# rc360detector_102815.net
KiCad netlist of a schematic drawn in EAGLE
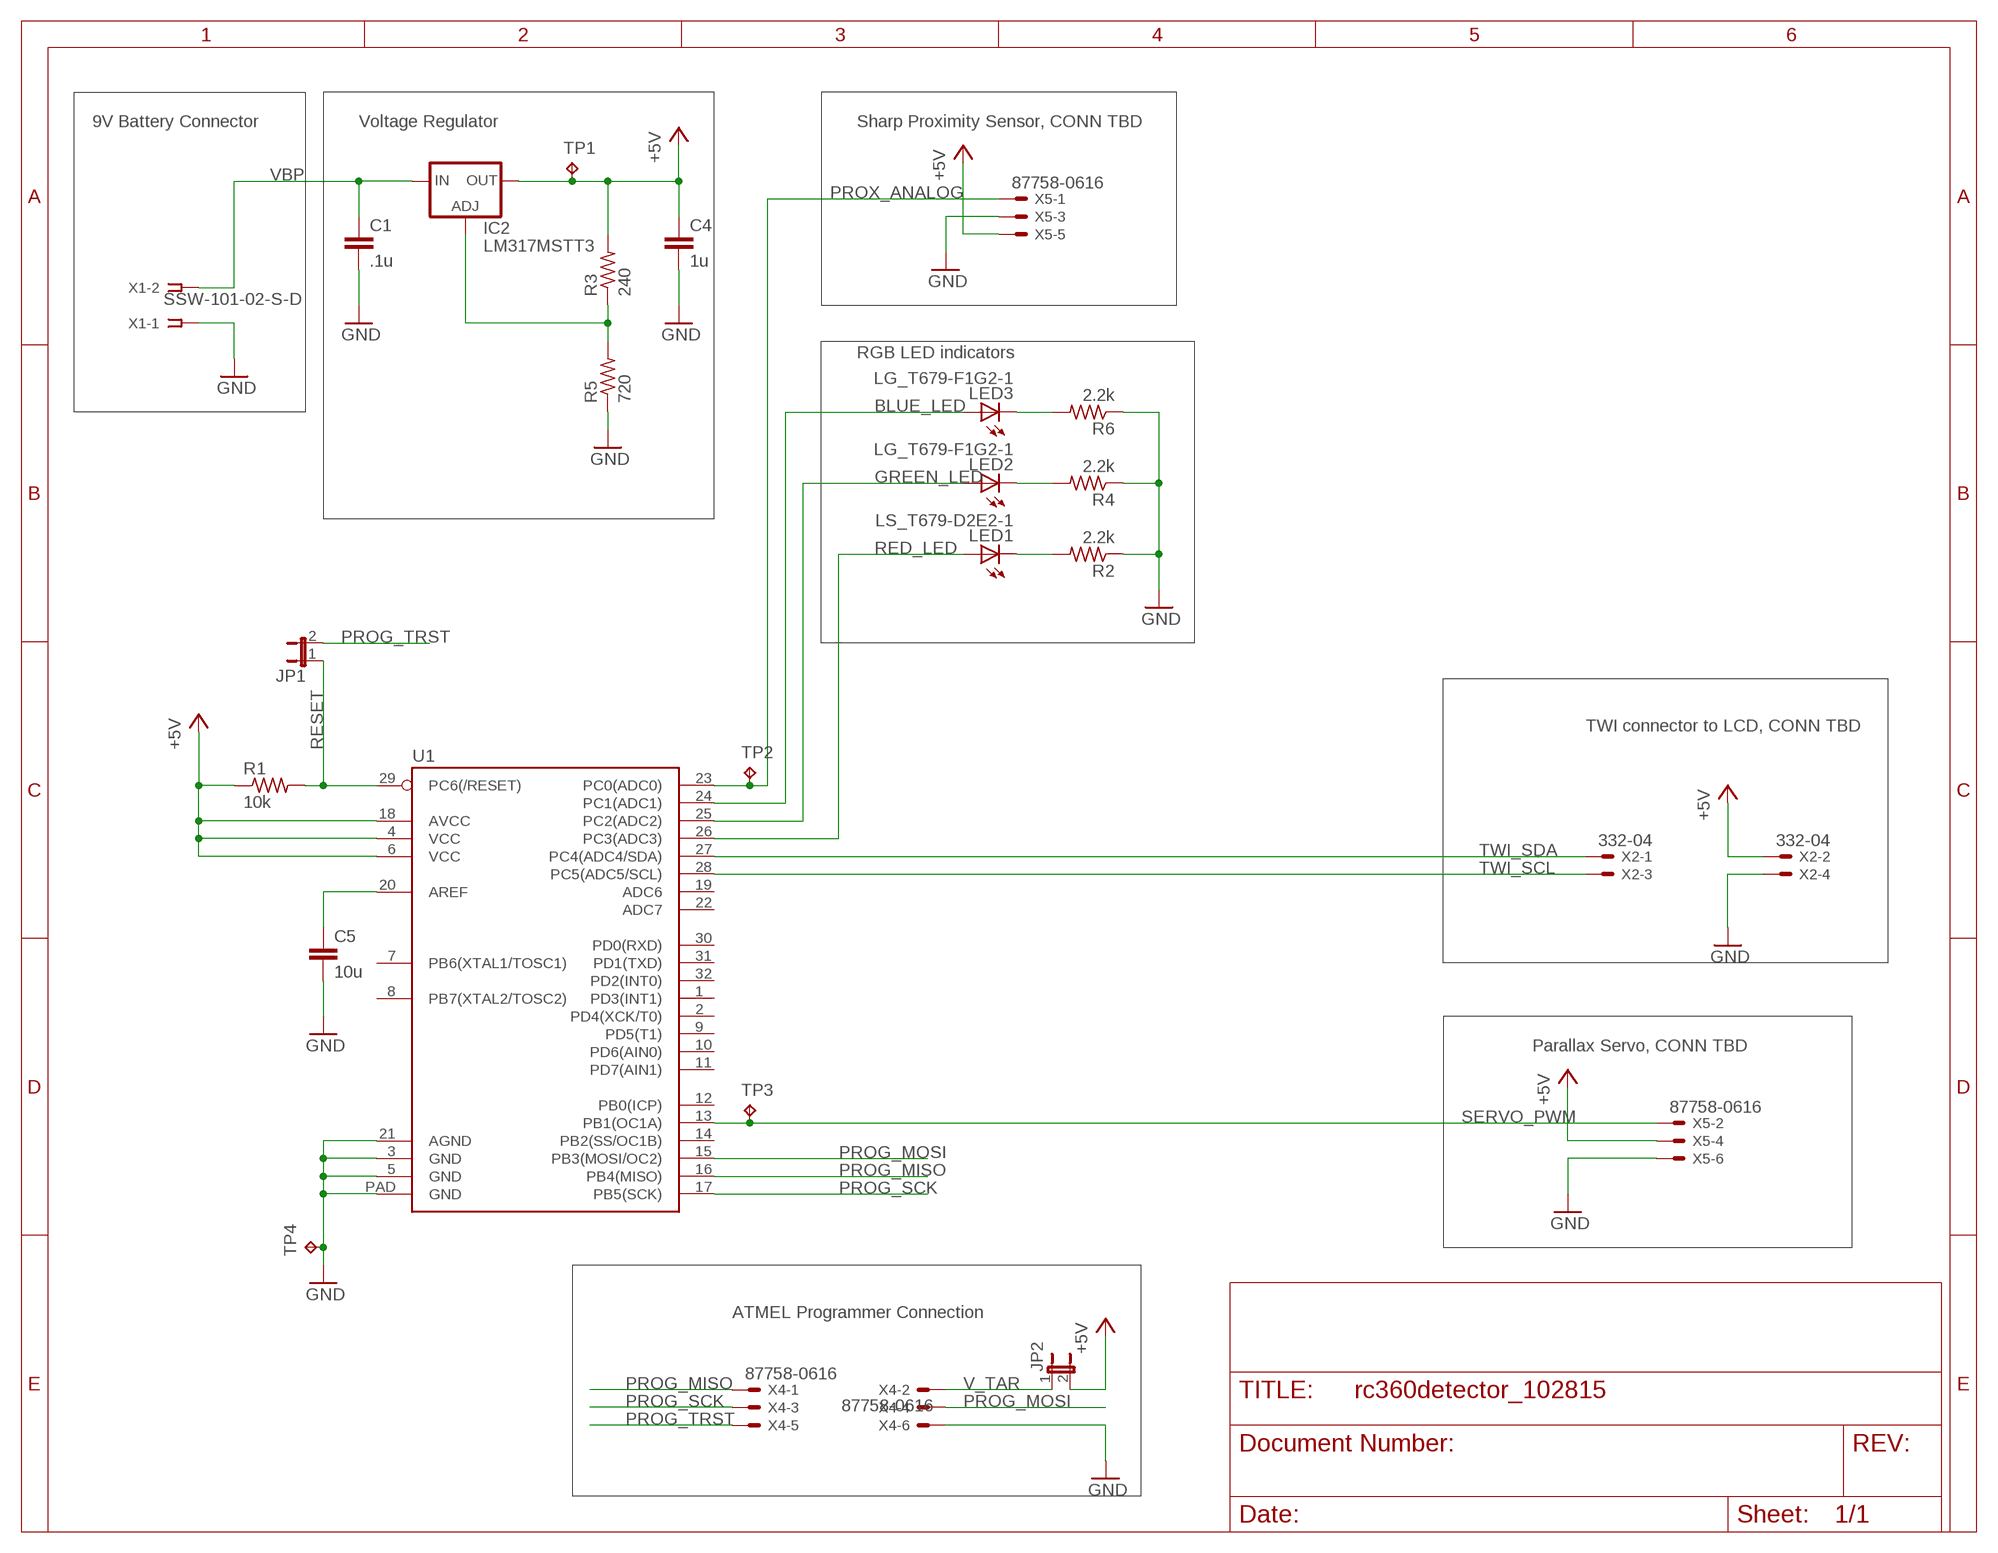
[diagram p0: schematic, sheet 1]

(export (version "E")
  (design (tool "Eeschema 10.0.6"))
  (components
    (comp (ref "C1")
      (value ".1u")
      (footprint "eagle-import:C0603")
      (libsource (lib "eagle-import") (part "C-EUC0603"))
    )
    (comp (ref "C4")
      (value "1u")
      (footprint "eagle-import:C0603")
      (libsource (lib "eagle-import") (part "C-EUC0603"))
    )
    (comp (ref "C5")
      (value "10u")
      (footprint "eagle-import:C0603")
      (libsource (lib "eagle-import") (part "C-EUC0603"))
    )
    (comp (ref "IC2")
      (value "LM317MSTT3")
      (footprint "eagle-import:SOT223")
      (libsource (lib "eagle-import") (part "LM317?MSTT3"))
    )
    (comp (ref "JP1")
      (value "JP1E")
      (footprint "eagle-import:JP1")
      (libsource (lib "eagle-import") (part "JP1E"))
    )
    (comp (ref "JP2")
      (value "JP1E")
      (footprint "eagle-import:JP1")
      (libsource (lib "eagle-import") (part "JP1E"))
    )
    (comp (ref "LED1")
      (value "LS_T679-D2E2-1")
      (footprint "eagle-import:PLCC2")
      (libsource (lib "eagle-import") (part "_T679-?-1D2E2LS"))
    )
    (comp (ref "LED2")
      (value "LG_T679-F1G2-1")
      (footprint "eagle-import:PLCC2")
      (libsource (lib "eagle-import") (part "_T679-?-1F1G2LG"))
    )
    (comp (ref "LED3")
      (value "LG_T679-F1G2-1")
      (footprint "eagle-import:PLCC2")
      (libsource (lib "eagle-import") (part "_T679-?-1F1G2LG"))
    )
    (comp (ref "R1")
      (value "10k")
      (footprint "eagle-import:R0603")
      (libsource (lib "eagle-import") (part "R-US_R0603"))
    )
    (comp (ref "R2")
      (value "2.2k")
      (footprint "eagle-import:R0805")
      (libsource (lib "eagle-import") (part "R-US_R0805"))
    )
    (comp (ref "R3")
      (value "240")
      (footprint "eagle-import:R0603")
      (libsource (lib "eagle-import") (part "R-US_R0603"))
    )
    (comp (ref "R4")
      (value "2.2k")
      (footprint "eagle-import:R0805")
      (libsource (lib "eagle-import") (part "R-US_R0805"))
    )
    (comp (ref "R5")
      (value "720")
      (footprint "eagle-import:R0603")
      (libsource (lib "eagle-import") (part "R-US_R0603"))
    )
    (comp (ref "R6")
      (value "2.2k")
      (footprint "eagle-import:R0805")
      (libsource (lib "eagle-import") (part "R-US_R0805"))
    )
    (comp (ref "TP1")
      (value "TPPAD1-17")
      (footprint "eagle-import:P1-17")
      (libsource (lib "eagle-import") (part "TPPAD1-17"))
    )
    (comp (ref "TP2")
      (value "TPPAD1-17")
      (footprint "eagle-import:P1-17")
      (libsource (lib "eagle-import") (part "TPPAD1-17"))
    )
    (comp (ref "TP3")
      (value "TPPAD1-17")
      (footprint "eagle-import:P1-17")
      (libsource (lib "eagle-import") (part "TPPAD1-17"))
    )
    (comp (ref "TP4")
      (value "TPPAD1-17")
      (footprint "eagle-import:P1-17")
      (libsource (lib "eagle-import") (part "TPPAD1-17"))
    )
    (comp (ref "U1")
      (value "ATMEGA328P_MLFMLF32")
      (footprint "eagle-import:MLF32-PAD")
      (libsource (lib "eagle-import") (part "ATMEGA328P_MLFMLF32"))
    )
    (comp (ref "X1")
      (value "SSW-101-02-S-D")
      (footprint "eagle-import:SSW-101-02-S-D")
      (libsource (lib "eagle-import") (part "SSW-101-02-S-D"))
    )
    (comp (ref "X2")
      (value "332-04")
      (footprint "eagle-import:332-04")
      (libsource (lib "eagle-import") (part "332-04"))
    )
    (comp (ref "X4")
      (value "87758-0616")
      (footprint "eagle-import:87758-0616")
      (libsource (lib "eagle-import") (part "87758-0616"))
    )
    (comp (ref "X5")
      (value "87758-0616")
      (footprint "eagle-import:87758-0616")
      (libsource (lib "eagle-import") (part "87758-0616"))
    )
  )
  (nets
    (net (code "1") (name "+5V") (class "Default")
      (node (ref "C4") (pin "1") (pinfunction "1_1") (pintype "passive"))
      (node (ref "IC2") (pin "4") (pinfunction "OUT_4") (pintype "passive"))
      (node (ref "JP2") (pin "2") (pinfunction "2_2") (pintype "passive"))
      (node (ref "R1") (pin "1") (pinfunction "1_1") (pintype "passive"))
      (node (ref "R3") (pin "2") (pinfunction "2_2") (pintype "passive"))
      (node (ref "TP1") (pin "TP") (pinfunction "TP_TP") (pintype "input"))
      (node (ref "U1") (pin "18") (pinfunction "AVCC_18") (pintype "bidirectional"))
      (node (ref "U1") (pin "4") (pinfunction "VCC_4") (pintype "bidirectional"))
      (node (ref "U1") (pin "6") (pinfunction "VCC_6") (pintype "bidirectional"))
      (node (ref "X2") (pin "2") (pinfunction "S_2") (pintype "passive"))
      (node (ref "X5") (pin "4") (pinfunction "S_4") (pintype "passive"))
      (node (ref "X5") (pin "5") (pinfunction "S_5") (pintype "passive"))
    )
    (net (code "2") (name "/BLUE_LED") (class "Default")
      (node (ref "LED3") (pin "A") (pinfunction "A_A") (pintype "passive"))
      (node (ref "U1") (pin "24") (pinfunction "PC1(ADC1)_24") (pintype "bidirectional"))
    )
    (net (code "3") (name "/GREEN_LED") (class "Default")
      (node (ref "LED2") (pin "A") (pinfunction "A_A") (pintype "passive"))
      (node (ref "U1") (pin "25") (pinfunction "PC2(ADC2)_25") (pintype "bidirectional"))
    )
    (net (code "4") (name "/PROG_MISO") (class "Default")
      (node (ref "U1") (pin "16") (pinfunction "PB4(MISO)_16") (pintype "bidirectional"))
      (node (ref "X4") (pin "1") (pinfunction "S_1") (pintype "passive"))
    )
    (net (code "5") (name "/PROG_MOSI") (class "Default")
      (node (ref "U1") (pin "15") (pinfunction "PB3(MOSI/OC2)_15") (pintype "bidirectional"))
      (node (ref "X4") (pin "4") (pinfunction "S_4") (pintype "passive"))
    )
    (net (code "6") (name "/PROG_SCK") (class "Default")
      (node (ref "U1") (pin "17") (pinfunction "PB5(SCK)_17") (pintype "bidirectional"))
      (node (ref "X4") (pin "3") (pinfunction "S_3") (pintype "passive"))
    )
    (net (code "7") (name "/PROG_TRST") (class "Default")
      (node (ref "JP1") (pin "2") (pinfunction "2_2") (pintype "passive"))
      (node (ref "X4") (pin "5") (pinfunction "S_5") (pintype "passive"))
    )
    (net (code "8") (name "/PROX_ANALOG") (class "Default")
      (node (ref "TP2") (pin "TP") (pinfunction "TP_TP") (pintype "input"))
      (node (ref "U1") (pin "23") (pinfunction "PC0(ADC0)_23") (pintype "bidirectional"))
      (node (ref "X5") (pin "1") (pinfunction "S_1") (pintype "passive"))
    )
    (net (code "9") (name "/RED_LED") (class "Default")
      (node (ref "LED1") (pin "A") (pinfunction "A_A") (pintype "passive"))
      (node (ref "U1") (pin "26") (pinfunction "PC3(ADC3)_26") (pintype "bidirectional"))
    )
    (net (code "10") (name "/RESET") (class "Default")
      (node (ref "JP1") (pin "1") (pinfunction "1_1") (pintype "passive"))
      (node (ref "R1") (pin "2") (pinfunction "2_2") (pintype "passive"))
      (node (ref "U1") (pin "29") (pinfunction "PC6(/RESET)_29") (pintype "bidirectional"))
    )
    (net (code "11") (name "/SERVO_PWM") (class "Default")
      (node (ref "TP3") (pin "TP") (pinfunction "TP_TP") (pintype "input"))
      (node (ref "U1") (pin "13") (pinfunction "PB1(OC1A)_13") (pintype "bidirectional"))
      (node (ref "X5") (pin "2") (pinfunction "S_2") (pintype "passive"))
    )
    (net (code "12") (name "/TWI_SCL") (class "Default")
      (node (ref "U1") (pin "28") (pinfunction "PC5(ADC5/SCL)_28") (pintype "bidirectional"))
      (node (ref "X2") (pin "3") (pinfunction "S_3") (pintype "passive"))
    )
    (net (code "13") (name "/TWI_SDA") (class "Default")
      (node (ref "U1") (pin "27") (pinfunction "PC4(ADC4/SDA)_27") (pintype "bidirectional"))
      (node (ref "X2") (pin "1") (pinfunction "S_1") (pintype "passive"))
    )
    (net (code "14") (name "/VBP") (class "Default")
      (node (ref "C1") (pin "1") (pinfunction "1_1") (pintype "passive"))
      (node (ref "IC2") (pin "3") (pinfunction "IN_3") (pintype "input"))
      (node (ref "X1") (pin "2") (pinfunction "1_2") (pintype "passive"))
    )
    (net (code "15") (name "/V_TAR") (class "Default")
      (node (ref "JP2") (pin "1") (pinfunction "1_1") (pintype "passive"))
      (node (ref "X4") (pin "2") (pinfunction "S_2") (pintype "passive"))
    )
    (net (code "16") (name "GND") (class "Default")
      (node (ref "C1") (pin "2") (pinfunction "2_2") (pintype "passive"))
      (node (ref "C4") (pin "2") (pinfunction "2_2") (pintype "passive"))
      (node (ref "C5") (pin "2") (pinfunction "2_2") (pintype "passive"))
      (node (ref "R2") (pin "1") (pinfunction "1_1") (pintype "passive"))
      (node (ref "R4") (pin "1") (pinfunction "1_1") (pintype "passive"))
      (node (ref "R5") (pin "1") (pinfunction "1_1") (pintype "passive"))
      (node (ref "R6") (pin "1") (pinfunction "1_1") (pintype "passive"))
      (node (ref "TP4") (pin "TP") (pinfunction "TP_TP") (pintype "input"))
      (node (ref "U1") (pin "21") (pinfunction "AGND_21") (pintype "bidirectional"))
      (node (ref "U1") (pin "3") (pinfunction "GND_3") (pintype "bidirectional"))
      (node (ref "U1") (pin "5") (pinfunction "GND_5") (pintype "bidirectional"))
      (node (ref "U1") (pin "PAD") (pinfunction "GND_PAD") (pintype "bidirectional"))
      (node (ref "X1") (pin "1") (pinfunction "1_1") (pintype "passive"))
      (node (ref "X2") (pin "4") (pinfunction "S_4") (pintype "passive"))
      (node (ref "X4") (pin "6") (pinfunction "S_6") (pintype "passive"))
      (node (ref "X5") (pin "3") (pinfunction "S_3") (pintype "passive"))
      (node (ref "X5") (pin "6") (pinfunction "S_6") (pintype "passive"))
    )
    (net (code "17") (name "Net-(IC2-ADJ)") (class "Default")
      (node (ref "IC2") (pin "1") (pinfunction "ADJ_1") (pintype "input"))
      (node (ref "R3") (pin "1") (pinfunction "1_1") (pintype "passive"))
      (node (ref "R5") (pin "2") (pinfunction "2_2") (pintype "passive"))
    )
    (net (code "18") (name "Net-(LED1-PadC)") (class "Default")
      (node (ref "LED1") (pin "C") (pinfunction "C_C") (pintype "passive"))
      (node (ref "R2") (pin "2") (pinfunction "2_2") (pintype "passive"))
    )
    (net (code "19") (name "Net-(LED2-PadC)") (class "Default")
      (node (ref "LED2") (pin "C") (pinfunction "C_C") (pintype "passive"))
      (node (ref "R4") (pin "2") (pinfunction "2_2") (pintype "passive"))
    )
    (net (code "20") (name "Net-(LED3-PadC)") (class "Default")
      (node (ref "LED3") (pin "C") (pinfunction "C_C") (pintype "passive"))
      (node (ref "R6") (pin "2") (pinfunction "2_2") (pintype "passive"))
    )
    (net (code "21") (name "Net-(U1-AREF)") (class "Default")
      (node (ref "C5") (pin "1") (pinfunction "1_1") (pintype "passive"))
      (node (ref "U1") (pin "20") (pinfunction "AREF_20") (pintype "bidirectional"))
    )
    (net (code "22") (name "unconnected-(U1-ADC6-Pad19)") (class "Default")
      (node (ref "U1") (pin "19") (pinfunction "ADC6_19") (pintype "bidirectional"))
    )
    (net (code "23") (name "unconnected-(U1-ADC7-Pad22)") (class "Default")
      (node (ref "U1") (pin "22") (pinfunction "ADC7_22") (pintype "bidirectional"))
    )
    (net (code "24") (name "unconnected-(U1-PB0(ICP)-Pad12)") (class "Default")
      (node (ref "U1") (pin "12") (pinfunction "PB0(ICP)_12") (pintype "bidirectional"))
    )
    (net (code "25") (name "unconnected-(U1-PB2(SS{slash}OC1B)-Pad14)") (class "Default")
      (node (ref "U1") (pin "14") (pinfunction "PB2(SS/OC1B)_14") (pintype "bidirectional"))
    )
    (net (code "26") (name "unconnected-(U1-PB6(XTAL1{slash}TOSC1)-Pad7)") (class "Default")
      (node (ref "U1") (pin "7") (pinfunction "PB6(XTAL1/TOSC1)_7") (pintype "bidirectional"))
    )
    (net (code "27") (name "unconnected-(U1-PB7(XTAL2{slash}TOSC2)-Pad8)") (class "Default")
      (node (ref "U1") (pin "8") (pinfunction "PB7(XTAL2/TOSC2)_8") (pintype "bidirectional"))
    )
    (net (code "28") (name "unconnected-(U1-PD0(RXD)-Pad30)") (class "Default")
      (node (ref "U1") (pin "30") (pinfunction "PD0(RXD)_30") (pintype "bidirectional"))
    )
    (net (code "29") (name "unconnected-(U1-PD1(TXD)-Pad31)") (class "Default")
      (node (ref "U1") (pin "31") (pinfunction "PD1(TXD)_31") (pintype "bidirectional"))
    )
    (net (code "30") (name "unconnected-(U1-PD2(INT0)-Pad32)") (class "Default")
      (node (ref "U1") (pin "32") (pinfunction "PD2(INT0)_32") (pintype "bidirectional"))
    )
    (net (code "31") (name "unconnected-(U1-PD3(INT1)-Pad1)") (class "Default")
      (node (ref "U1") (pin "1") (pinfunction "PD3(INT1)_1") (pintype "bidirectional"))
    )
    (net (code "32") (name "unconnected-(U1-PD4(XCK{slash}T0)-Pad2)") (class "Default")
      (node (ref "U1") (pin "2") (pinfunction "PD4(XCK/T0)_2") (pintype "bidirectional"))
    )
    (net (code "33") (name "unconnected-(U1-PD5(T1)-Pad9)") (class "Default")
      (node (ref "U1") (pin "9") (pinfunction "PD5(T1)_9") (pintype "bidirectional"))
    )
    (net (code "34") (name "unconnected-(U1-PD6(AIN0)-Pad10)") (class "Default")
      (node (ref "U1") (pin "10") (pinfunction "PD6(AIN0)_10") (pintype "bidirectional"))
    )
    (net (code "35") (name "unconnected-(U1-PD7(AIN1)-Pad11)") (class "Default")
      (node (ref "U1") (pin "11") (pinfunction "PD7(AIN1)_11") (pintype "bidirectional"))
    )
  )
)
